# thermoshield.net
KiCad netlist of a schematic drawn in EAGLE
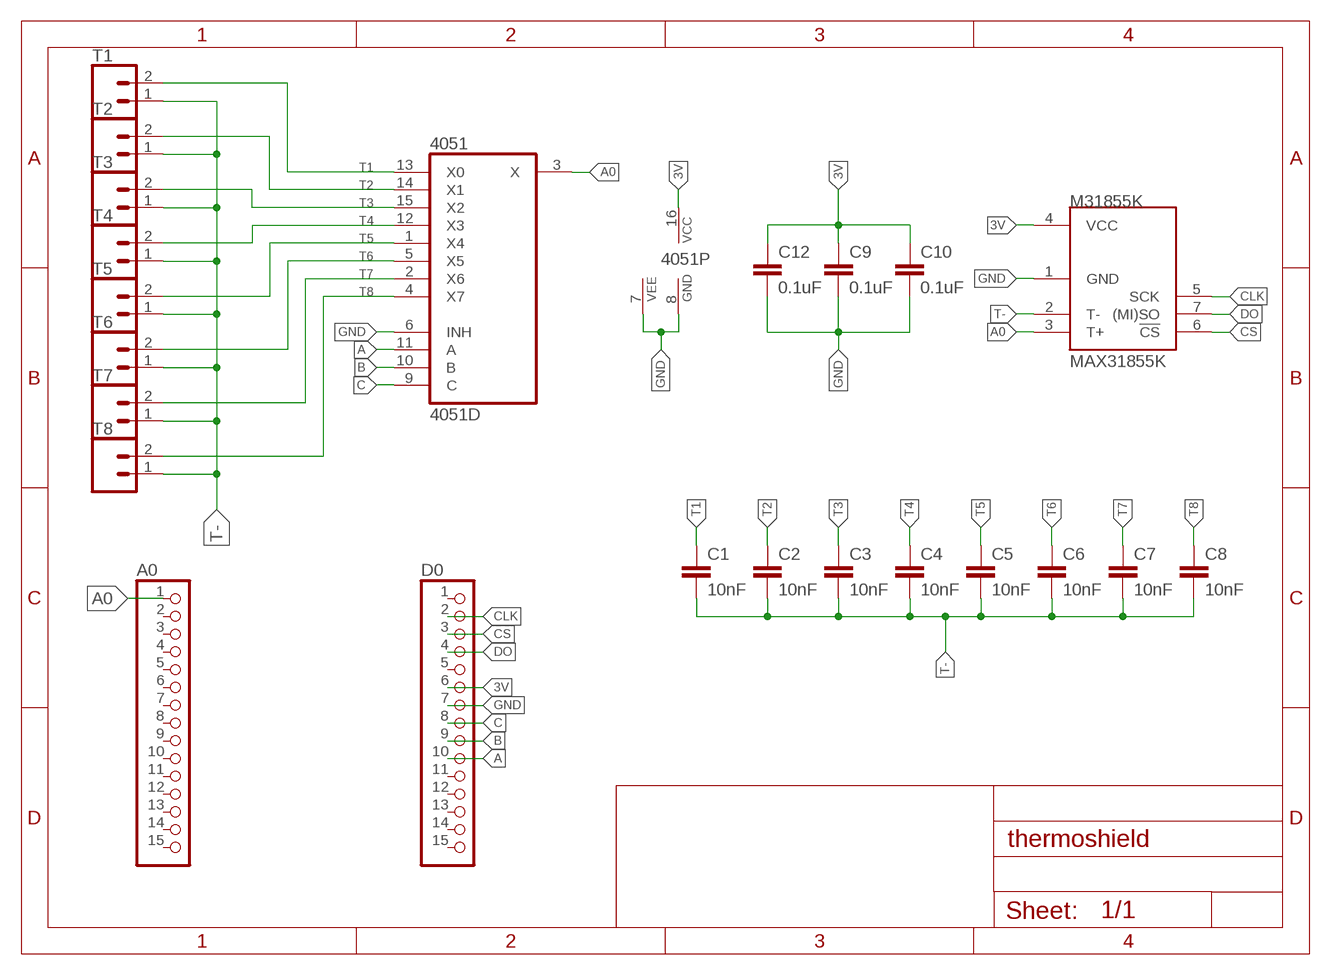
[diagram p0: schematic, sheet 1]

(export (version "E")
  (design (tool "Eeschema 10.0.6"))
  (components
    (comp (ref "4051")
      (value "4051D")
      (footprint "eagle-import:SO16")
      (fields (field (name "SPICEPREFIX") "X"))
      (libsource (lib "eagle-import") (part "4051D"))
    )
    (comp (ref "A0")
      (value "PINHD-1X15")
      (footprint "eagle-import:1X15")
      (libsource (lib "eagle-import") (part "PINHD-1X15"))
    )
    (comp (ref "C1")
      (value "10nF")
      (footprint "eagle-import:0603")
      (libsource (lib "eagle-import") (part "10NF-0603-50V-10%"))
    )
    (comp (ref "C2")
      (value "10nF")
      (footprint "eagle-import:0603")
      (libsource (lib "eagle-import") (part "10NF-0603-50V-10%"))
    )
    (comp (ref "C3")
      (value "10nF")
      (footprint "eagle-import:0603")
      (libsource (lib "eagle-import") (part "10NF-0603-50V-10%"))
    )
    (comp (ref "C4")
      (value "10nF")
      (footprint "eagle-import:0603")
      (libsource (lib "eagle-import") (part "10NF-0603-50V-10%"))
    )
    (comp (ref "C5")
      (value "10nF")
      (footprint "eagle-import:0603")
      (libsource (lib "eagle-import") (part "10NF-0603-50V-10%"))
    )
    (comp (ref "C6")
      (value "10nF")
      (footprint "eagle-import:0603")
      (libsource (lib "eagle-import") (part "10NF-0603-50V-10%"))
    )
    (comp (ref "C7")
      (value "10nF")
      (footprint "eagle-import:0603")
      (libsource (lib "eagle-import") (part "10NF-0603-50V-10%"))
    )
    (comp (ref "C8")
      (value "10nF")
      (footprint "eagle-import:0603")
      (libsource (lib "eagle-import") (part "10NF-0603-50V-10%"))
    )
    (comp (ref "C9")
      (value "0.1uF")
      (footprint "eagle-import:0603")
      (libsource (lib "eagle-import") (part "0.1UF-0603-25V-(+80/-20%)"))
    )
    (comp (ref "C10")
      (value "0.1uF")
      (footprint "eagle-import:0603")
      (libsource (lib "eagle-import") (part "0.1UF-0603-25V-(+80/-20%)"))
    )
    (comp (ref "C12")
      (value "0.1uF")
      (footprint "eagle-import:0603")
      (libsource (lib "eagle-import") (part "0.1UF-0603-25V-(+80/-20%)"))
    )
    (comp (ref "D0")
      (value "PINHD-1X15")
      (footprint "eagle-import:1X15")
      (libsource (lib "eagle-import") (part "PINHD-1X15"))
    )
    (comp (ref "M31855K")
      (value "MAX31855K")
      (footprint "eagle-import:SO08")
      (libsource (lib "eagle-import") (part "MAX31855K"))
    )
    (comp (ref "T1")
      (value "CONN_023.5MM-NO_SILK")
      (footprint "eagle-import:SCREWTERMINAL-3.5MM-2-NS")
      (libsource (lib "eagle-import") (part "CONN_023.5MM-NO_SILK"))
    )
    (comp (ref "T2")
      (value "CONN_023.5MM-NO_SILK")
      (footprint "eagle-import:SCREWTERMINAL-3.5MM-2-NS")
      (libsource (lib "eagle-import") (part "CONN_023.5MM-NO_SILK"))
    )
    (comp (ref "T3")
      (value "CONN_023.5MM-NO_SILK")
      (footprint "eagle-import:SCREWTERMINAL-3.5MM-2-NS")
      (libsource (lib "eagle-import") (part "CONN_023.5MM-NO_SILK"))
    )
    (comp (ref "T4")
      (value "CONN_023.5MM-NO_SILK")
      (footprint "eagle-import:SCREWTERMINAL-3.5MM-2-NS")
      (libsource (lib "eagle-import") (part "CONN_023.5MM-NO_SILK"))
    )
    (comp (ref "T5")
      (value "CONN_023.5MM-NO_SILK")
      (footprint "eagle-import:SCREWTERMINAL-3.5MM-2-NS")
      (libsource (lib "eagle-import") (part "CONN_023.5MM-NO_SILK"))
    )
    (comp (ref "T6")
      (value "CONN_023.5MM-NO_SILK")
      (footprint "eagle-import:SCREWTERMINAL-3.5MM-2-NS")
      (libsource (lib "eagle-import") (part "CONN_023.5MM-NO_SILK"))
    )
    (comp (ref "T7")
      (value "CONN_023.5MM-NO_SILK")
      (footprint "eagle-import:SCREWTERMINAL-3.5MM-2-NS")
      (libsource (lib "eagle-import") (part "CONN_023.5MM-NO_SILK"))
    )
    (comp (ref "T8")
      (value "CONN_023.5MM-NO_SILK")
      (footprint "eagle-import:SCREWTERMINAL-3.5MM-2-NS")
      (libsource (lib "eagle-import") (part "CONN_023.5MM-NO_SILK"))
    )
  )
  (nets
    (net (code "1") (name "3V") (class "Default")
      (node (ref "4051") (pin "16") (pinfunction "VCC_16") (pintype "power_in"))
      (node (ref "C10") (pin "1") (pinfunction "1_1") (pintype "passive"))
      (node (ref "C12") (pin "1") (pinfunction "1_1") (pintype "passive"))
      (node (ref "C9") (pin "1") (pinfunction "1_1") (pintype "passive"))
      (node (ref "D0") (pin "6") (pinfunction "6_6") (pintype "passive"))
      (node (ref "M31855K") (pin "4") (pinfunction "VCC_4") (pintype "bidirectional"))
    )
    (net (code "2") (name "A") (class "Default")
      (node (ref "4051") (pin "11") (pinfunction "A_11") (pintype "input"))
      (node (ref "D0") (pin "10") (pinfunction "10_10") (pintype "passive"))
    )
    (net (code "3") (name "A0") (class "Default")
      (node (ref "4051") (pin "3") (pinfunction "X_3") (pintype "bidirectional"))
      (node (ref "A0") (pin "1") (pinfunction "1_1") (pintype "passive"))
      (node (ref "M31855K") (pin "3") (pinfunction "T+_3") (pintype "bidirectional"))
    )
    (net (code "4") (name "B") (class "Default")
      (node (ref "4051") (pin "10") (pinfunction "B_10") (pintype "input"))
      (node (ref "D0") (pin "9") (pinfunction "9_9") (pintype "passive"))
    )
    (net (code "5") (name "C") (class "Default")
      (node (ref "4051") (pin "9") (pinfunction "C_9") (pintype "input"))
      (node (ref "D0") (pin "8") (pinfunction "8_8") (pintype "passive"))
    )
    (net (code "6") (name "CLK") (class "Default")
      (node (ref "D0") (pin "2") (pinfunction "2_2") (pintype "passive"))
      (node (ref "M31855K") (pin "5") (pinfunction "SCK_5") (pintype "bidirectional"))
    )
    (net (code "7") (name "CS") (class "Default")
      (node (ref "D0") (pin "3") (pinfunction "3_3") (pintype "passive"))
      (node (ref "M31855K") (pin "6") (pinfunction "~{CS}_6") (pintype "bidirectional"))
    )
    (net (code "8") (name "DO") (class "Default")
      (node (ref "D0") (pin "4") (pinfunction "4_4") (pintype "passive"))
      (node (ref "M31855K") (pin "7") (pinfunction "(MI)SO_7") (pintype "bidirectional"))
    )
    (net (code "9") (name "GND") (class "Default")
      (node (ref "4051") (pin "6") (pinfunction "INH_6") (pintype "input"))
      (node (ref "4051") (pin "7") (pinfunction "VEE_7") (pintype "power_in"))
      (node (ref "4051") (pin "8") (pinfunction "GND_8") (pintype "power_in"))
      (node (ref "C10") (pin "2") (pinfunction "2_2") (pintype "passive"))
      (node (ref "C12") (pin "2") (pinfunction "2_2") (pintype "passive"))
      (node (ref "C9") (pin "2") (pinfunction "2_2") (pintype "passive"))
      (node (ref "D0") (pin "7") (pinfunction "7_7") (pintype "passive"))
      (node (ref "M31855K") (pin "1") (pinfunction "GND_1") (pintype "bidirectional"))
    )
    (net (code "10") (name "T-") (class "Default")
      (node (ref "C1") (pin "2") (pinfunction "2_2") (pintype "passive"))
      (node (ref "C2") (pin "2") (pinfunction "2_2") (pintype "passive"))
      (node (ref "C3") (pin "2") (pinfunction "2_2") (pintype "passive"))
      (node (ref "C4") (pin "2") (pinfunction "2_2") (pintype "passive"))
      (node (ref "C5") (pin "2") (pinfunction "2_2") (pintype "passive"))
      (node (ref "C6") (pin "2") (pinfunction "2_2") (pintype "passive"))
      (node (ref "C7") (pin "2") (pinfunction "2_2") (pintype "passive"))
      (node (ref "C8") (pin "2") (pinfunction "2_2") (pintype "passive"))
      (node (ref "M31855K") (pin "2") (pinfunction "T-_2") (pintype "bidirectional"))
      (node (ref "T1") (pin "1") (pinfunction "1_1") (pintype "passive"))
      (node (ref "T2") (pin "1") (pinfunction "1_1") (pintype "passive"))
      (node (ref "T3") (pin "1") (pinfunction "1_1") (pintype "passive"))
      (node (ref "T4") (pin "1") (pinfunction "1_1") (pintype "passive"))
      (node (ref "T5") (pin "1") (pinfunction "1_1") (pintype "passive"))
      (node (ref "T6") (pin "1") (pinfunction "1_1") (pintype "passive"))
      (node (ref "T7") (pin "1") (pinfunction "1_1") (pintype "passive"))
      (node (ref "T8") (pin "1") (pinfunction "1_1") (pintype "passive"))
    )
    (net (code "11") (name "T1") (class "Default")
      (node (ref "4051") (pin "13") (pinfunction "X0_13") (pintype "bidirectional"))
      (node (ref "C1") (pin "1") (pinfunction "1_1") (pintype "passive"))
      (node (ref "T1") (pin "2") (pinfunction "2_2") (pintype "passive"))
    )
    (net (code "12") (name "T2") (class "Default")
      (node (ref "4051") (pin "14") (pinfunction "X1_14") (pintype "bidirectional"))
      (node (ref "C2") (pin "1") (pinfunction "1_1") (pintype "passive"))
      (node (ref "T2") (pin "2") (pinfunction "2_2") (pintype "passive"))
    )
    (net (code "13") (name "T3") (class "Default")
      (node (ref "4051") (pin "15") (pinfunction "X2_15") (pintype "bidirectional"))
      (node (ref "C3") (pin "1") (pinfunction "1_1") (pintype "passive"))
      (node (ref "T3") (pin "2") (pinfunction "2_2") (pintype "passive"))
    )
    (net (code "14") (name "T4") (class "Default")
      (node (ref "4051") (pin "12") (pinfunction "X3_12") (pintype "bidirectional"))
      (node (ref "C4") (pin "1") (pinfunction "1_1") (pintype "passive"))
      (node (ref "T4") (pin "2") (pinfunction "2_2") (pintype "passive"))
    )
    (net (code "15") (name "T5") (class "Default")
      (node (ref "4051") (pin "1") (pinfunction "X4_1") (pintype "bidirectional"))
      (node (ref "C5") (pin "1") (pinfunction "1_1") (pintype "passive"))
      (node (ref "T5") (pin "2") (pinfunction "2_2") (pintype "passive"))
    )
    (net (code "16") (name "T6") (class "Default")
      (node (ref "4051") (pin "5") (pinfunction "X5_5") (pintype "bidirectional"))
      (node (ref "C6") (pin "1") (pinfunction "1_1") (pintype "passive"))
      (node (ref "T6") (pin "2") (pinfunction "2_2") (pintype "passive"))
    )
    (net (code "17") (name "T7") (class "Default")
      (node (ref "4051") (pin "2") (pinfunction "X6_2") (pintype "bidirectional"))
      (node (ref "C7") (pin "1") (pinfunction "1_1") (pintype "passive"))
      (node (ref "T7") (pin "2") (pinfunction "2_2") (pintype "passive"))
    )
    (net (code "18") (name "T8") (class "Default")
      (node (ref "4051") (pin "4") (pinfunction "X7_4") (pintype "bidirectional"))
      (node (ref "C8") (pin "1") (pinfunction "1_1") (pintype "passive"))
      (node (ref "T8") (pin "2") (pinfunction "2_2") (pintype "passive"))
    )
    (net (code "19") (name "unconnected-(A0-Pad2)") (class "Default")
      (node (ref "A0") (pin "2") (pinfunction "2_2") (pintype "passive"))
    )
    (net (code "20") (name "unconnected-(A0-Pad3)") (class "Default")
      (node (ref "A0") (pin "3") (pinfunction "3_3") (pintype "passive"))
    )
    (net (code "21") (name "unconnected-(A0-Pad4)") (class "Default")
      (node (ref "A0") (pin "4") (pinfunction "4_4") (pintype "passive"))
    )
    (net (code "22") (name "unconnected-(A0-Pad5)") (class "Default")
      (node (ref "A0") (pin "5") (pinfunction "5_5") (pintype "passive"))
    )
    (net (code "23") (name "unconnected-(A0-Pad6)") (class "Default")
      (node (ref "A0") (pin "6") (pinfunction "6_6") (pintype "passive"))
    )
    (net (code "24") (name "unconnected-(A0-Pad7)") (class "Default")
      (node (ref "A0") (pin "7") (pinfunction "7_7") (pintype "passive"))
    )
    (net (code "25") (name "unconnected-(A0-Pad8)") (class "Default")
      (node (ref "A0") (pin "8") (pinfunction "8_8") (pintype "passive"))
    )
    (net (code "26") (name "unconnected-(A0-Pad9)") (class "Default")
      (node (ref "A0") (pin "9") (pinfunction "9_9") (pintype "passive"))
    )
    (net (code "27") (name "unconnected-(A0-Pad10)") (class "Default")
      (node (ref "A0") (pin "10") (pinfunction "10_10") (pintype "passive"))
    )
    (net (code "28") (name "unconnected-(A0-Pad11)") (class "Default")
      (node (ref "A0") (pin "11") (pinfunction "11_11") (pintype "passive"))
    )
    (net (code "29") (name "unconnected-(A0-Pad12)") (class "Default")
      (node (ref "A0") (pin "12") (pinfunction "12_12") (pintype "passive"))
    )
    (net (code "30") (name "unconnected-(A0-Pad13)") (class "Default")
      (node (ref "A0") (pin "13") (pinfunction "13_13") (pintype "passive"))
    )
    (net (code "31") (name "unconnected-(A0-Pad14)") (class "Default")
      (node (ref "A0") (pin "14") (pinfunction "14_14") (pintype "passive"))
    )
    (net (code "32") (name "unconnected-(A0-Pad15)") (class "Default")
      (node (ref "A0") (pin "15") (pinfunction "15_15") (pintype "passive"))
    )
    (net (code "33") (name "unconnected-(D0-Pad1)") (class "Default")
      (node (ref "D0") (pin "1") (pinfunction "1_1") (pintype "passive"))
    )
    (net (code "34") (name "unconnected-(D0-Pad5)") (class "Default")
      (node (ref "D0") (pin "5") (pinfunction "5_5") (pintype "passive"))
    )
    (net (code "35") (name "unconnected-(D0-Pad11)") (class "Default")
      (node (ref "D0") (pin "11") (pinfunction "11_11") (pintype "passive"))
    )
    (net (code "36") (name "unconnected-(D0-Pad12)") (class "Default")
      (node (ref "D0") (pin "12") (pinfunction "12_12") (pintype "passive"))
    )
    (net (code "37") (name "unconnected-(D0-Pad13)") (class "Default")
      (node (ref "D0") (pin "13") (pinfunction "13_13") (pintype "passive"))
    )
    (net (code "38") (name "unconnected-(D0-Pad14)") (class "Default")
      (node (ref "D0") (pin "14") (pinfunction "14_14") (pintype "passive"))
    )
    (net (code "39") (name "unconnected-(D0-Pad15)") (class "Default")
      (node (ref "D0") (pin "15") (pinfunction "15_15") (pintype "passive"))
    )
  )
)
